# ROOT.net
KiCad netlist of a schematic drawn in Altium Designer
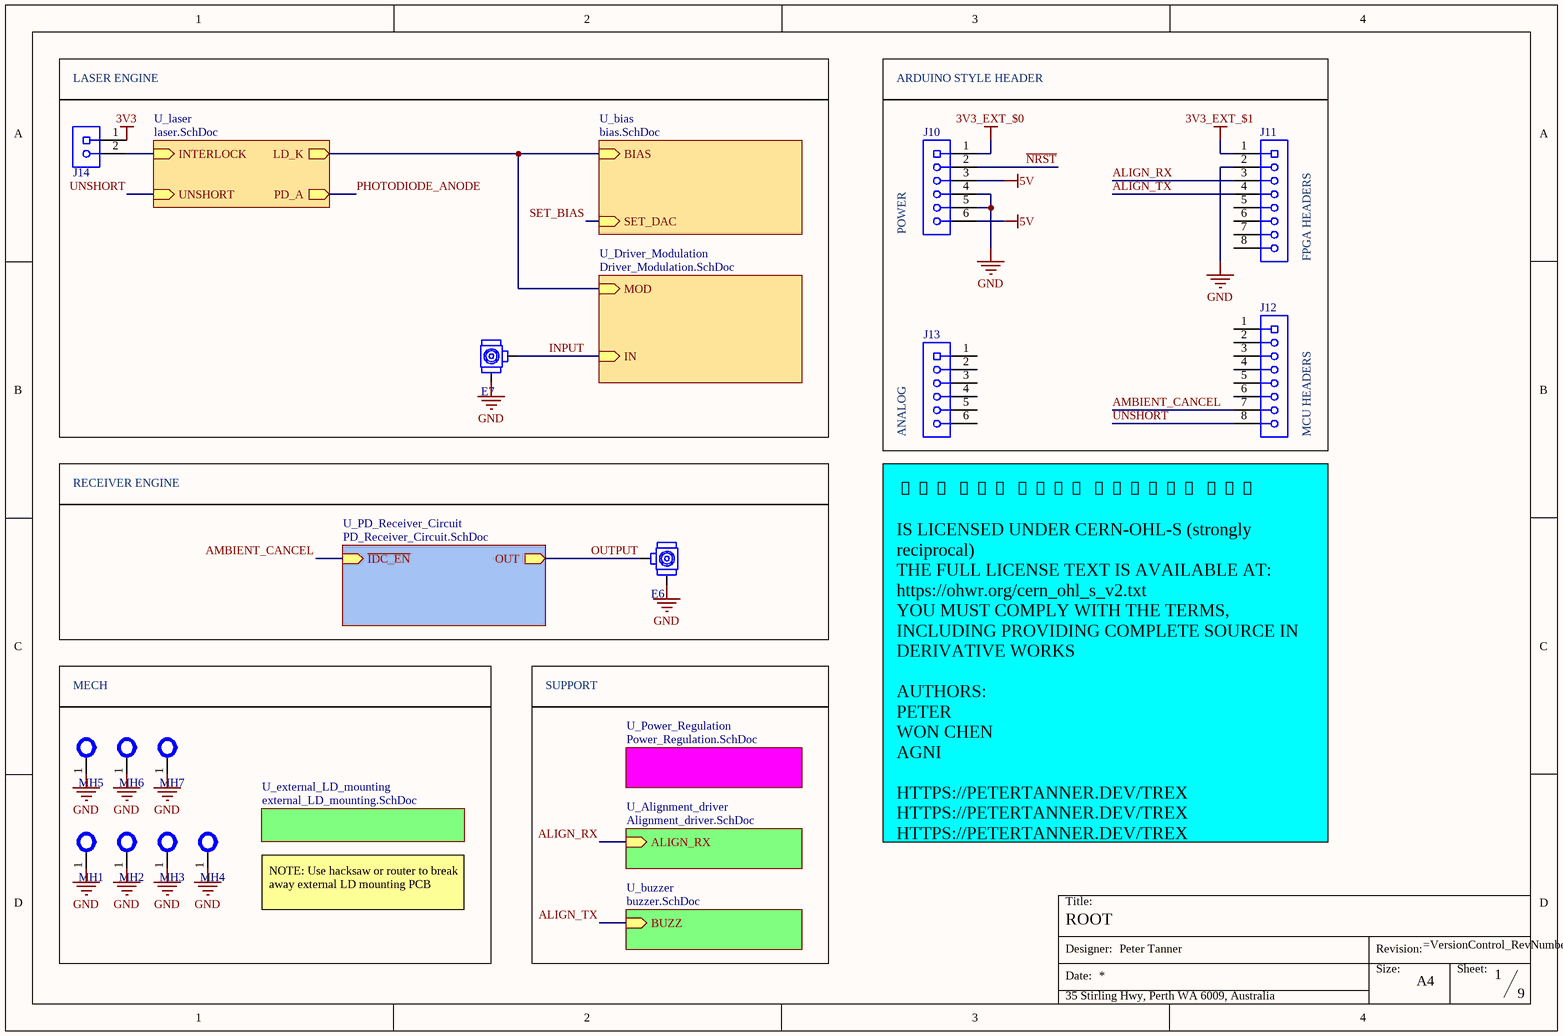
[diagram p0: ROOT.SchDoc]

(export (version "E")
  (design (tool "Eeschema 10.0.6"))
  (components
    (comp (ref "E6")
      (value "U.FL-R-SMT-1(01)")
      (footprint "HRS-U.FL-R-SMT-3_V 4_LAYER_KO")
      (description "Rf Connectors / Coaxial Connectors SMT Ml Rec Au 50 Ohm W/anti Sldr Wicking UFL")
      (fields (field (name "SOURCE") "UWAA_Stock"))
      (libsource (lib "UWA Aerospace") (part "U.FL Connector"))
    )
    (comp (ref "E7")
      (value "U.FL-R-SMT-1(01)")
      (footprint "HRS-U.FL-R-SMT-3_V 4_LAYER_KO")
      (description "Rf Connectors / Coaxial Connectors SMT Ml Rec Au 50 Ohm W/anti Sldr Wicking UFL")
      (fields (field (name "SOURCE") "UWAA_Stock"))
      (libsource (lib "") (part "U.FL Connector_1"))
    )
    (comp (ref "J10")
      (value "68000-406HLF")
      (footprint "68000-406HLF-Footprint-1")
      (description "CONN HEADER 6POS .100 STR TIN")
      (fields (field (name "SOURCE") "Aliexpress"))
      (libsource (lib "UWA Aerospace") (part "68000-406HLF"))
    )
    (comp (ref "J11")
      (value "22-28-4080")
      (footprint "22-28-4080-Footprint-1")
      (description "Conn Unshrouded Header HDR 8 POS 2.54mm Solder ST Thru-Hole Bag")
      (fields (field (name "SOURCE") "Aliexpress"))
      (libsource (lib "UWA Aerospace") (part "Connector - 1x8 Single Sided"))
    )
    (comp (ref "J12")
      (value "22-28-4080")
      (footprint "22-28-4080-Footprint-1")
      (description "Conn Unshrouded Header HDR 8 POS 2.54mm Solder ST Thru-Hole Bag")
      (fields (field (name "SOURCE") "Aliexpress"))
      (libsource (lib "UWA Aerospace") (part "Connector - 1x8 Single Sided"))
    )
    (comp (ref "J13")
      (value "68000-406HLF")
      (footprint "68000-406HLF-Footprint-1")
      (description "CONN HEADER 6POS .100 STR TIN")
      (libsource (lib "UWA Aerospace") (part "68000-406HLF"))
    )
    (comp (ref "J14")
      (value "22-28-4020")
      (footprint "22-28-4020-Footprint-1")
      (description "KK 254 Breakaway Header, Vertical, 2 Circuits, Tin (Sn) Plating, Mating Pin Length 6.09mm 2 POS")
      (fields (field (name "SOURCE") "Aliexpress"))
      (libsource (lib "UWA Aerospace") (part "22-28-4020"))
    )
    (comp (ref "MH1")
      (value "Mounting hole M3")
      (footprint "Mounting hole M3-Footprint-1")
      (description "Close fit Di3.2 mm Alt: M3 nut flange")
      (libsource (lib "UWA Aerospace") (part "Hole_NO_BOM"))
    )
    (comp (ref "MH2")
      (value "Mounting hole M3")
      (footprint "Mounting hole M3-Footprint-1")
      (description "Close fit Di3.2 mm Alt: M3 nut flange")
      (libsource (lib "UWA Aerospace") (part "Hole_NO_BOM"))
    )
    (comp (ref "MH3")
      (value "Mounting hole M3")
      (footprint "Mounting hole M3-Footprint-1")
      (description "Close fit Di3.2 mm Alt: M3 nut flange")
      (libsource (lib "UWA Aerospace") (part "Hole_NO_BOM"))
    )
    (comp (ref "MH4")
      (value "Mounting hole M3")
      (footprint "Mounting hole M3-Footprint-1")
      (description "Close fit Di3.2 mm Alt: M3 nut flange")
      (libsource (lib "UWA Aerospace") (part "Hole_NO_BOM"))
    )
    (comp (ref "MH5")
      (value "Mounting hole M3")
      (footprint "Mounting hole M3-Footprint-1")
      (description "Close fit Di3.2 mm Alt: M3 nut flange")
      (libsource (lib "UWA Aerospace") (part "Hole_NO_BOM"))
    )
    (comp (ref "MH6")
      (value "Mounting hole M3")
      (footprint "Mounting hole M3-Footprint-1")
      (description "Close fit Di3.2 mm Alt: M3 nut flange")
      (libsource (lib "UWA Aerospace") (part "Hole_NO_BOM"))
    )
    (comp (ref "MH7")
      (value "Mounting hole M3")
      (footprint "Mounting hole M3-Footprint-1")
      (description "Close fit Di3.2 mm Alt: M3 nut flange")
      (libsource (lib "UWA Aerospace") (part "Hole_NO_BOM"))
    )
  )
  (nets
    (net (code "1") (name "/ALIGN_RX") (class "Default")
      (node (ref "J11") (pin "3") (pinfunction "3_3") (pintype "passive"))
    )
    (net (code "2") (name "/ALIGN_TX") (class "Default")
      (node (ref "J11") (pin "4") (pinfunction "4_4") (pintype "passive"))
    )
    (net (code "3") (name "/AMBIENT_CANCEL") (class "Default")
      (node (ref "J12") (pin "7") (pinfunction "7_7") (pintype "passive"))
    )
    (net (code "4") (name "/INPUT") (class "Default")
      (node (ref "E7") (pin "1") (pinfunction "SIG_1") (pintype "passive"))
    )
    (net (code "5") (name "/INTERLOCK") (class "Default")
      (node (ref "J14") (pin "2") (pinfunction "2_2") (pintype "passive"))
    )
    (net (code "7") (name "/OUTPUT") (class "Default")
      (node (ref "E6") (pin "1") (pinfunction "SIG_1") (pintype "passive"))
    )
    (net (code "10") (name "/UNSHORT") (class "Default")
      (node (ref "J12") (pin "8") (pinfunction "8_8") (pintype "passive"))
    )
    (net (code "11") (name "/~{NRST}") (class "Default")
      (node (ref "J10") (pin "2") (pinfunction "2_2") (pintype "passive"))
    )
    (net (code "12") (name "3V3") (class "Default")
      (node (ref "J14") (pin "1") (pinfunction "1_1") (pintype "passive"))
    )
    (net (code "13") (name "3V3_EXT_$0") (class "Default")
      (node (ref "J10") (pin "1") (pinfunction "1_1") (pintype "passive"))
    )
    (net (code "14") (name "3V3_EXT_$1") (class "Default")
      (node (ref "J11") (pin "1") (pinfunction "1_1") (pintype "passive"))
    )
    (net (code "15") (name "5V") (class "Default")
      (node (ref "J10") (pin "3") (pinfunction "3_3") (pintype "passive"))
      (node (ref "J10") (pin "6") (pinfunction "6_6") (pintype "passive"))
    )
    (net (code "16") (name "GND") (class "Default")
      (node (ref "E6") (pin "2") (pinfunction "GND_2") (pintype "passive"))
      (node (ref "E7") (pin "2") (pinfunction "GND_2") (pintype "passive"))
      (node (ref "J10") (pin "4") (pinfunction "4_4") (pintype "passive"))
      (node (ref "J10") (pin "5") (pinfunction "5_5") (pintype "passive"))
      (node (ref "J11") (pin "2") (pinfunction "2_2") (pintype "passive"))
      (node (ref "MH1") (pin "1") (pintype "passive"))
      (node (ref "MH2") (pin "1") (pintype "passive"))
      (node (ref "MH3") (pin "1") (pintype "passive"))
      (node (ref "MH4") (pin "1") (pintype "passive"))
      (node (ref "MH5") (pin "1") (pintype "passive"))
      (node (ref "MH6") (pin "1") (pintype "passive"))
      (node (ref "MH7") (pin "1") (pintype "passive"))
    )
    (net (code "17") (name "unconnected-(J11-Pad5)") (class "Default")
      (node (ref "J11") (pin "5") (pinfunction "5_5") (pintype "passive"))
    )
    (net (code "18") (name "unconnected-(J11-Pad6)") (class "Default")
      (node (ref "J11") (pin "6") (pinfunction "6_6") (pintype "passive"))
    )
    (net (code "19") (name "unconnected-(J11-Pad7)") (class "Default")
      (node (ref "J11") (pin "7") (pinfunction "7_7") (pintype "passive"))
    )
    (net (code "20") (name "unconnected-(J11-Pad8)") (class "Default")
      (node (ref "J11") (pin "8") (pinfunction "8_8") (pintype "passive"))
    )
    (net (code "21") (name "unconnected-(J12-Pad1)") (class "Default")
      (node (ref "J12") (pin "1") (pinfunction "1_1") (pintype "passive"))
    )
    (net (code "22") (name "unconnected-(J12-Pad2)") (class "Default")
      (node (ref "J12") (pin "2") (pinfunction "2_2") (pintype "passive"))
    )
    (net (code "23") (name "unconnected-(J12-Pad3)") (class "Default")
      (node (ref "J12") (pin "3") (pinfunction "3_3") (pintype "passive"))
    )
    (net (code "24") (name "unconnected-(J12-Pad4)") (class "Default")
      (node (ref "J12") (pin "4") (pinfunction "4_4") (pintype "passive"))
    )
    (net (code "25") (name "unconnected-(J12-Pad5)") (class "Default")
      (node (ref "J12") (pin "5") (pinfunction "5_5") (pintype "passive"))
    )
    (net (code "26") (name "unconnected-(J12-Pad6)") (class "Default")
      (node (ref "J12") (pin "6") (pinfunction "6_6") (pintype "passive"))
    )
    (net (code "27") (name "unconnected-(J13-Pad1)") (class "Default")
      (node (ref "J13") (pin "1") (pinfunction "1_1") (pintype "passive"))
    )
    (net (code "28") (name "unconnected-(J13-Pad2)") (class "Default")
      (node (ref "J13") (pin "2") (pinfunction "2_2") (pintype "passive"))
    )
    (net (code "29") (name "unconnected-(J13-Pad3)") (class "Default")
      (node (ref "J13") (pin "3") (pinfunction "3_3") (pintype "passive"))
    )
    (net (code "30") (name "unconnected-(J13-Pad4)") (class "Default")
      (node (ref "J13") (pin "4") (pinfunction "4_4") (pintype "passive"))
    )
    (net (code "31") (name "unconnected-(J13-Pad5)") (class "Default")
      (node (ref "J13") (pin "5") (pinfunction "5_5") (pintype "passive"))
    )
    (net (code "32") (name "unconnected-(J13-Pad6)") (class "Default")
      (node (ref "J13") (pin "6") (pinfunction "6_6") (pintype "passive"))
    )
  )
)
